# Sheet1.net
KiCad netlist of a schematic drawn in Altium Designer
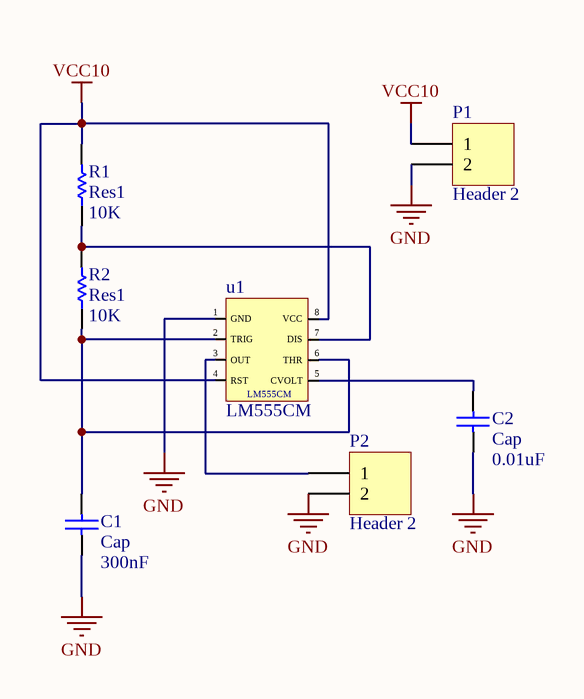
[diagram p0: Sheet1.SchDoc]

(export (version "E")
  (design (tool "Eeschema 10.0.6"))
  (components
    (comp (ref "C1")
      (value "Cap")
      (footprint "RAD-0.3")
      (description "Capacitor")
      (fields (field (name "ALTIUM_VALUE") "300nF") (field (name "PUBLISHER") "Altium Limited"))
      (libsource (lib "Miscellaneous Devices") (part "Cap"))
    )
    (comp (ref "C2")
      (value "Cap")
      (footprint "RAD-0.3")
      (description "Capacitor")
      (fields (field (name "ALTIUM_VALUE") "0.01uF") (field (name "PUBLISHER") "Altium Limited"))
      (libsource (lib "Miscellaneous Devices") (part "Cap"))
    )
    (comp (ref "P1")
      (value "Header 2")
      (footprint "HDR1X2")
      (description "Header, 2-Pin")
      (fields (field (name "PUBLISHER") "Altium Limited"))
      (libsource (lib "Miscellaneous Connectors") (part "Header 2"))
    )
    (comp (ref "P2")
      (value "Header 2")
      (footprint "HDR1X2")
      (description "Header, 2-Pin")
      (fields (field (name "PUBLISHER") "Altium Limited"))
      (libsource (lib "Miscellaneous Connectors") (part "Header 2"))
    )
    (comp (ref "R1")
      (value "Res1")
      (footprint "AXIAL-0.3")
      (description "Resistor")
      (fields (field (name "ALTIUM_VALUE") "10K") (field (name "PUBLISHER") "Altium Limited"))
      (libsource (lib "Miscellaneous Devices") (part "Res1"))
    )
    (comp (ref "R2")
      (value "Res1")
      (footprint "AXIAL-0.3")
      (description "Resistor")
      (fields (field (name "ALTIUM_VALUE") "10K") (field (name "PUBLISHER") "Altium Limited"))
      (libsource (lib "Miscellaneous Devices") (part "Res1"))
    )
    (comp (ref "u1")
      (value "LM555CM")
      (footprint "LM555CM")
      (description "LM555CM IC")
      (fields (field (name "CREATED BY") "Cyrine SFAR"))
      (libsource (lib "LM555CM1") (part "LM555CM"))
    )
  )
  (nets
    (net (code "1") (name "GND") (class "Default")
      (node (ref "C1") (pin "1") (pinfunction "1_1") (pintype "passive"))
      (node (ref "C2") (pin "1") (pinfunction "1_1") (pintype "passive"))
      (node (ref "P1") (pin "2") (pinfunction "2_2") (pintype "passive"))
      (node (ref "P2") (pin "2") (pinfunction "2_2") (pintype "passive"))
      (node (ref "u1") (pin "1") (pinfunction "GND_1") (pintype "passive"))
    )
    (net (code "2") (name "Net-(u1-CVOLT)") (class "Default")
      (node (ref "C2") (pin "2") (pinfunction "2_2") (pintype "passive"))
      (node (ref "u1") (pin "5") (pinfunction "CVOLT_5") (pintype "passive"))
    )
    (net (code "3") (name "Net-(u1-DIS)") (class "Default")
      (node (ref "R1") (pin "1") (pinfunction "1_1") (pintype "passive"))
      (node (ref "R2") (pin "2") (pinfunction "2_2") (pintype "passive"))
      (node (ref "u1") (pin "7") (pinfunction "DIS_7") (pintype "passive"))
    )
    (net (code "4") (name "Net-(u1-OUT)") (class "Default")
      (node (ref "P2") (pin "1") (pinfunction "1_1") (pintype "passive"))
      (node (ref "u1") (pin "3") (pinfunction "OUT_3") (pintype "passive"))
    )
    (net (code "5") (name "Net-(u1-THR)") (class "Default")
      (node (ref "C1") (pin "2") (pinfunction "2_2") (pintype "passive"))
      (node (ref "R2") (pin "1") (pinfunction "1_1") (pintype "passive"))
      (node (ref "u1") (pin "2") (pinfunction "TRIG_2") (pintype "passive"))
      (node (ref "u1") (pin "6") (pinfunction "THR_6") (pintype "passive"))
    )
    (net (code "6") (name "VCC10") (class "Default")
      (node (ref "P1") (pin "1") (pinfunction "1_1") (pintype "passive"))
      (node (ref "R1") (pin "2") (pinfunction "2_2") (pintype "passive"))
      (node (ref "u1") (pin "4") (pinfunction "RST_4") (pintype "passive"))
      (node (ref "u1") (pin "8") (pinfunction "VCC_8") (pintype "passive"))
    )
  )
)
